# LVSevenSegmentDriver.net
KiCad netlist of a schematic drawn in EAGLE
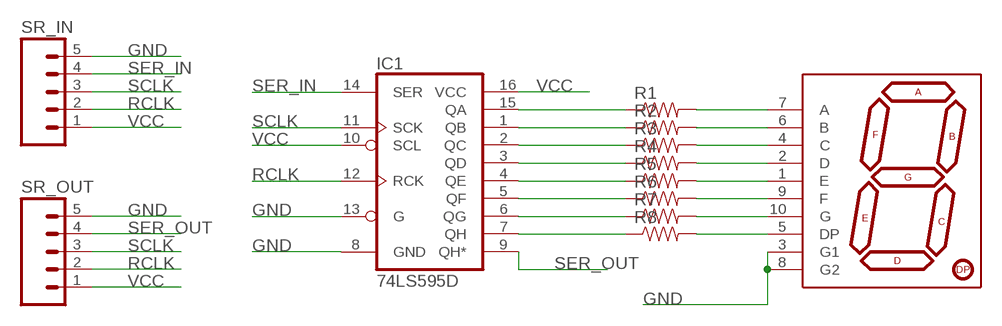
[diagram p0: schematic, sheet 1]

(export (version "E")
  (design (tool "Eeschema 10.0.6"))
  (components
    (comp (ref "IC1")
      (value "74LS595D")
      (footprint "eagle-import:SO16")
      (libsource (lib "eagle-import") (part "74595DLS"))
    )
    (comp (ref "R1")
      (value "RESISTOR1206")
      (footprint "eagle-import:1206")
      (libsource (lib "eagle-import") (part "RESISTOR1206"))
    )
    (comp (ref "R2")
      (value "RESISTOR1206")
      (footprint "eagle-import:1206")
      (libsource (lib "eagle-import") (part "RESISTOR1206"))
    )
    (comp (ref "R3")
      (value "RESISTOR1206")
      (footprint "eagle-import:1206")
      (libsource (lib "eagle-import") (part "RESISTOR1206"))
    )
    (comp (ref "R4")
      (value "RESISTOR1206")
      (footprint "eagle-import:1206")
      (libsource (lib "eagle-import") (part "RESISTOR1206"))
    )
    (comp (ref "R5")
      (value "RESISTOR1206")
      (footprint "eagle-import:1206")
      (libsource (lib "eagle-import") (part "RESISTOR1206"))
    )
    (comp (ref "R6")
      (value "RESISTOR1206")
      (footprint "eagle-import:1206")
      (libsource (lib "eagle-import") (part "RESISTOR1206"))
    )
    (comp (ref "R7")
      (value "RESISTOR1206")
      (footprint "eagle-import:1206")
      (libsource (lib "eagle-import") (part "RESISTOR1206"))
    )
    (comp (ref "R8")
      (value "RESISTOR1206")
      (footprint "eagle-import:1206")
      (libsource (lib "eagle-import") (part "RESISTOR1206"))
    )
    (comp (ref "SR_IN")
      (value "M05PTH")
      (footprint "eagle-import:1X05")
      (libsource (lib "eagle-import") (part "M05PTH"))
    )
    (comp (ref "SR_OUT")
      (value "M05PTH")
      (footprint "eagle-import:1X05")
      (libsource (lib "eagle-import") (part "M05PTH"))
    )
    (comp (ref "U$1")
      (value "7-SEGMENT-DISPLAY-1\"-REDEZ")
      (footprint "eagle-import:7-SEGMENT-1_PTH-EZ")
      (libsource (lib "eagle-import") (part "7-SEGMENT-DISPLAY-1{dblquote}-REDEZ"))
    )
  )
  (nets
    (net (code "1") (name "/GND") (class "Default")
      (node (ref "IC1") (pin "13") (pinfunction "G_13") (pintype "input"))
      (node (ref "IC1") (pin "8") (pinfunction "GND_8") (pintype "power_in"))
      (node (ref "SR_IN") (pin "5") (pinfunction "5_5") (pintype "passive"))
      (node (ref "SR_OUT") (pin "5") (pinfunction "5_5") (pintype "passive"))
      (node (ref "U$1") (pin "3") (pinfunction "G1_3") (pintype "bidirectional"))
      (node (ref "U$1") (pin "8") (pinfunction "G2_8") (pintype "bidirectional"))
    )
    (net (code "2") (name "/RCLK") (class "Default")
      (node (ref "IC1") (pin "12") (pinfunction "RCK_12") (pintype "input"))
      (node (ref "SR_IN") (pin "2") (pinfunction "2_2") (pintype "passive"))
      (node (ref "SR_OUT") (pin "2") (pinfunction "2_2") (pintype "passive"))
    )
    (net (code "3") (name "/SCLK") (class "Default")
      (node (ref "IC1") (pin "11") (pinfunction "SCK_11") (pintype "input"))
      (node (ref "SR_IN") (pin "3") (pinfunction "3_3") (pintype "passive"))
      (node (ref "SR_OUT") (pin "3") (pinfunction "3_3") (pintype "passive"))
    )
    (net (code "4") (name "/SER_IN") (class "Default")
      (node (ref "IC1") (pin "14") (pinfunction "SER_14") (pintype "input"))
      (node (ref "SR_IN") (pin "4") (pinfunction "4_4") (pintype "passive"))
    )
    (net (code "5") (name "/SER_OUT") (class "Default")
      (node (ref "IC1") (pin "9") (pinfunction "QH*_9") (pintype "tri_state"))
      (node (ref "SR_OUT") (pin "4") (pinfunction "4_4") (pintype "passive"))
    )
    (net (code "6") (name "/VCC") (class "Default")
      (node (ref "IC1") (pin "10") (pinfunction "SCL_10") (pintype "input"))
      (node (ref "IC1") (pin "16") (pinfunction "VCC_16") (pintype "power_in"))
      (node (ref "SR_IN") (pin "1") (pinfunction "1_1") (pintype "passive"))
      (node (ref "SR_OUT") (pin "1") (pinfunction "1_1") (pintype "passive"))
    )
    (net (code "7") (name "Net-(IC1-QA)") (class "Default")
      (node (ref "IC1") (pin "15") (pinfunction "QA_15") (pintype "tri_state"))
      (node (ref "R1") (pin "1") (pinfunction "1_1") (pintype "passive"))
    )
    (net (code "8") (name "Net-(IC1-QB)") (class "Default")
      (node (ref "IC1") (pin "1") (pinfunction "QB_1") (pintype "tri_state"))
      (node (ref "R2") (pin "1") (pinfunction "1_1") (pintype "passive"))
    )
    (net (code "9") (name "Net-(IC1-QC)") (class "Default")
      (node (ref "IC1") (pin "2") (pinfunction "QC_2") (pintype "tri_state"))
      (node (ref "R3") (pin "1") (pinfunction "1_1") (pintype "passive"))
    )
    (net (code "10") (name "Net-(IC1-QD)") (class "Default")
      (node (ref "IC1") (pin "3") (pinfunction "QD_3") (pintype "tri_state"))
      (node (ref "R4") (pin "1") (pinfunction "1_1") (pintype "passive"))
    )
    (net (code "11") (name "Net-(IC1-QE)") (class "Default")
      (node (ref "IC1") (pin "4") (pinfunction "QE_4") (pintype "tri_state"))
      (node (ref "R5") (pin "1") (pinfunction "1_1") (pintype "passive"))
    )
    (net (code "12") (name "Net-(IC1-QF)") (class "Default")
      (node (ref "IC1") (pin "5") (pinfunction "QF_5") (pintype "tri_state"))
      (node (ref "R6") (pin "1") (pinfunction "1_1") (pintype "passive"))
    )
    (net (code "13") (name "Net-(IC1-QG)") (class "Default")
      (node (ref "IC1") (pin "6") (pinfunction "QG_6") (pintype "tri_state"))
      (node (ref "R7") (pin "1") (pinfunction "1_1") (pintype "passive"))
    )
    (net (code "14") (name "Net-(IC1-QH)") (class "Default")
      (node (ref "IC1") (pin "7") (pinfunction "QH_7") (pintype "tri_state"))
      (node (ref "R8") (pin "1") (pinfunction "1_1") (pintype "passive"))
    )
    (net (code "15") (name "Net-(U$1-A)") (class "Default")
      (node (ref "R1") (pin "2") (pinfunction "2_2") (pintype "passive"))
      (node (ref "U$1") (pin "7") (pinfunction "A_7") (pintype "bidirectional"))
    )
    (net (code "16") (name "Net-(U$1-B)") (class "Default")
      (node (ref "R2") (pin "2") (pinfunction "2_2") (pintype "passive"))
      (node (ref "U$1") (pin "6") (pinfunction "B_6") (pintype "bidirectional"))
    )
    (net (code "17") (name "Net-(U$1-C)") (class "Default")
      (node (ref "R3") (pin "2") (pinfunction "2_2") (pintype "passive"))
      (node (ref "U$1") (pin "4") (pinfunction "C_4") (pintype "bidirectional"))
    )
    (net (code "18") (name "Net-(U$1-D)") (class "Default")
      (node (ref "R4") (pin "2") (pinfunction "2_2") (pintype "passive"))
      (node (ref "U$1") (pin "2") (pinfunction "D_2") (pintype "bidirectional"))
    )
    (net (code "19") (name "Net-(U$1-DP)") (class "Default")
      (node (ref "R8") (pin "2") (pinfunction "2_2") (pintype "passive"))
      (node (ref "U$1") (pin "5") (pinfunction "DP_5") (pintype "bidirectional"))
    )
    (net (code "20") (name "Net-(U$1-E)") (class "Default")
      (node (ref "R5") (pin "2") (pinfunction "2_2") (pintype "passive"))
      (node (ref "U$1") (pin "1") (pinfunction "E_1") (pintype "bidirectional"))
    )
    (net (code "21") (name "Net-(U$1-F)") (class "Default")
      (node (ref "R6") (pin "2") (pinfunction "2_2") (pintype "passive"))
      (node (ref "U$1") (pin "9") (pinfunction "F_9") (pintype "bidirectional"))
    )
    (net (code "22") (name "Net-(U$1-G)") (class "Default")
      (node (ref "R7") (pin "2") (pinfunction "2_2") (pintype "passive"))
      (node (ref "U$1") (pin "10") (pinfunction "G_10") (pintype "bidirectional"))
    )
  )
)
